# if-amp.net
KiCad netlist of a schematic drawn in Altium Designer
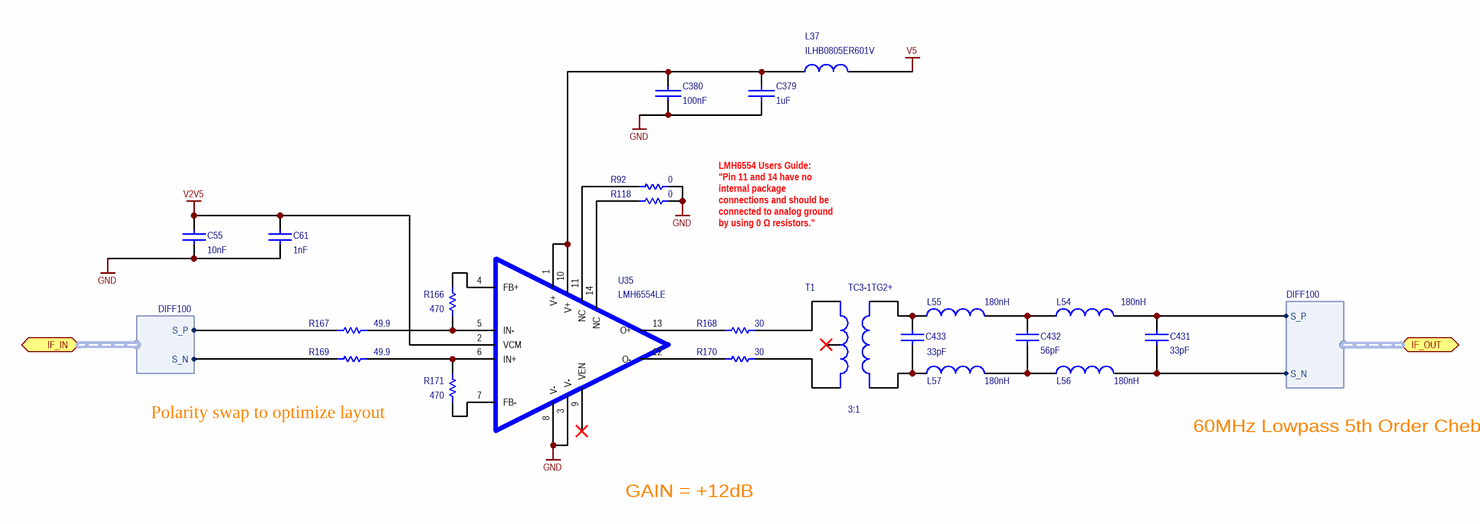
[diagram p0: if-amp.SchDoc]

(export (version "E")
  (design (tool "Eeschema 10.0.6"))
  (components
    (comp (ref "C55")
      (value "10nF")
      (footprint "generic:0402")
      (description "Ceramic Capacitor 10nF ±10% 25V X7R 0402")
      (fields (field (name "VOLTAGE") "25V") (field (name "MANUFACTURER") "Murata"))
      (libsource (lib "Graviton") (part "CAP 0402"))
    )
    (comp (ref "C61")
      (value "1nF")
      (footprint "generic:0402")
      (description "Ceramic Capacitor 1nF ±5% 50V NP0 0402")
      (fields (field (name "VOLTAGE") "50V") (field (name "MANUFACTURER") "Murata"))
      (libsource (lib "Graviton") (part "CAP 0402"))
    )
    (comp (ref "C379")
      (value "1uF")
      (footprint "generic:0402")
      (description "Ceramic Capacitor 1uF ±10% 10V X5R 0402")
      (fields (field (name "MANUFACTURER") "Murata") (field (name "TOLERANCE") "±10%"))
      (libsource (lib "*") (part "CAP"))
    )
    (comp (ref "C380")
      (value "100nF")
      (footprint "generic:0402")
      (description "Ceramic Capacitor 100nF ±10% 16V X7R 0402")
      (fields (field (name "MANUFACTURER") "Murata") (field (name "VOLTAGE") "16V"))
      (libsource (lib "*") (part "CAP"))
    )
    (comp (ref "C431")
      (value "33pF")
      (footprint "generic:0402")
      (description "Ceramic Capacitor 33pF ±5% 50V NP0 0402")
      (fields (field (name "VOLTAGE") "50V") (field (name "MANUFACTURER") "Murata"))
      (libsource (lib "Graviton") (part "CAP 0402"))
    )
    (comp (ref "C432")
      (value "56pF")
      (footprint "generic:0402")
      (description "Ceramic Capacitor 56pF ±5% 50V NP0 0402")
      (fields (field (name "VOLTAGE") "50V") (field (name "MANUFACTURER") "Murata"))
      (libsource (lib "Graviton") (part "CAP 0402"))
    )
    (comp (ref "C433")
      (value "33pF")
      (footprint "generic:0402")
      (description "Ceramic Capacitor 33pF ±5% 50V NP0 0402")
      (fields (field (name "VOLTAGE") "50V") (field (name "MANUFACTURER") "Murata"))
      (libsource (lib "Graviton") (part "CAP 0402"))
    )
    (comp (ref "L37")
      (value "ILHB0805ER601V")
      (footprint "0805")
      (description "Ferrite Bead 600-Ohm @ 100MHz 2A 0805")
      (fields (field (name "MANUFACTURER") "Vishay Dale") (field (name "TOLERANCE") "±25%"))
      (libsource (lib "*") (part "INDUCTANCE1"))
    )
    (comp (ref "L54")
      (value "180nH")
      (footprint "0603")
      (description "Inductor Wirewound 180nH ±2% 0603")
      (fields (field (name "MANUFACTURER") "Murata") (field (name "TOLERANCE") "±2%"))
      (libsource (lib "generic") (part "INDUCTOR"))
    )
    (comp (ref "L55")
      (value "180nH")
      (footprint "0603")
      (description "Inductor Wirewound 180nH ±2% 0603")
      (fields (field (name "MANUFACTURER") "Murata") (field (name "TOLERANCE") "±2%"))
      (libsource (lib "generic") (part "INDUCTOR"))
    )
    (comp (ref "L56")
      (value "180nH")
      (footprint "0603")
      (description "Inductor Wirewound 180nH ±2% 0603")
      (fields (field (name "MANUFACTURER") "Murata") (field (name "TOLERANCE") "±2%"))
      (libsource (lib "generic") (part "INDUCTOR"))
    )
    (comp (ref "L57")
      (value "180nH")
      (footprint "0603")
      (description "Inductor Wirewound 180nH ±2% 0603")
      (fields (field (name "MANUFACTURER") "Murata") (field (name "TOLERANCE") "±2%"))
      (libsource (lib "generic") (part "INDUCTOR"))
    )
    (comp (ref "R92")
      (value "0")
      (footprint "generic:0402")
      (description "Thick Film Resistor Jumper 0402")
      (fields (field (name "MANUFACTURER") "Panasonic") (field (name "Comment") "ERJ-2GE0R00X"))
      (libsource (lib "generic") (part "RES 0402"))
    )
    (comp (ref "R118")
      (value "0")
      (footprint "generic:0402")
      (description "Thick Film Resistor Jumper 0402")
      (fields (field (name "MANUFACTURER") "Panasonic") (field (name "Comment") "ERJ-2GE0R00X"))
      (libsource (lib "generic") (part "RES 0402"))
    )
    (comp (ref "R166")
      (value "470")
      (footprint "generic:0402")
      (description "Thin Film Resistor 470 ±0.1% 0402")
      (fields (field (name "MANUFACTURER") "Panasonic") (field (name "TOLERANCE") "±0.1%"))
      (libsource (lib "Graviton") (part "RES 0402"))
    )
    (comp (ref "R167")
      (value "49.9")
      (footprint "generic:0402")
      (description "Thin Film Resistor 49.9 ±0.1% 0402")
      (fields (field (name "MANUFACTURER") "Panasonic") (field (name "TOLERANCE") "±0.1%"))
      (libsource (lib "Graviton") (part "RES 0402"))
    )
    (comp (ref "R168")
      (value "30")
      (footprint "generic:0402")
      (description "Thin Film Resistor 30 ±0.1% 0402")
      (fields (field (name "MANUFACTURER") "TE Connectivity") (field (name "TOLERANCE") "0.1%"))
      (libsource (lib "Graviton") (part "RES 0402"))
    )
    (comp (ref "R169")
      (value "49.9")
      (footprint "generic:0402")
      (description "Thin Film Resistor 49.9 ±0.1% 0402")
      (fields (field (name "MANUFACTURER") "Panasonic") (field (name "TOLERANCE") "±0.1%"))
      (libsource (lib "Graviton") (part "RES 0402"))
    )
    (comp (ref "R170")
      (value "30")
      (footprint "generic:0402")
      (description "Thin Film Resistor 30 ±0.1% 0402")
      (fields (field (name "MANUFACTURER") "TE Connectivity") (field (name "TOLERANCE") "0.1%"))
      (libsource (lib "Graviton") (part "RES 0402"))
    )
    (comp (ref "R171")
      (value "470")
      (footprint "generic:0402")
      (description "Thin Film Resistor 470 ±0.1% 0402")
      (fields (field (name "MANUFACTURER") "Panasonic") (field (name "TOLERANCE") "±0.1%"))
      (libsource (lib "Graviton") (part "RES 0402"))
    )
    (comp (ref "T1")
      (value "3:1")
      (footprint "AT224-1A")
      (description "RF Transformer 0.4 to 500MHz SMD")
      (fields
        (field (name "MANUFACTURER P/N") "TC3-1TG2+")
        (field (name "MANUFACTURER") "Mini-Circuits")
        (field (name "Comment") "TC3-1TG2+")
      )
      (libsource (lib "phase4") (part "TC1-1TG2+"))
    )
    (comp (ref "U35")
      (value "LMH6554LE")
      (footprint "texas_instruments:NHJ0014A")
      (description "2.8 GHz Ultra Linear Fully Differential Amplifier")
      (fields (field (name "MANUFACTURER") "Texas Instruments"))
      (libsource (lib "ti") (part "LMH6554LE"))
    )
  )
  (nets
    (net (code "3") (name "GND") (class "Default")
      (node (ref "C379") (pin "1") (pinfunction "1_1") (pintype "passive"))
      (node (ref "C380") (pin "1") (pinfunction "1_1") (pintype "passive"))
      (node (ref "C55") (pin "1") (pinfunction "1_1") (pintype "passive"))
      (node (ref "C61") (pin "1") (pinfunction "1_1") (pintype "passive"))
      (node (ref "R118") (pin "2") (pinfunction "2_2") (pintype "passive"))
      (node (ref "R92") (pin "2") (pinfunction "2_2") (pintype "passive"))
      (node (ref "U35") (pin "3") (pinfunction "V-_3") (pintype "passive"))
      (node (ref "U35") (pin "8") (pinfunction "V-_8") (pintype "passive"))
    )
    (net (code "4") (name "Net-(C379-Pad2)") (class "Default")
      (node (ref "C379") (pin "2") (pinfunction "2_2") (pintype "passive"))
      (node (ref "C380") (pin "2") (pinfunction "2_2") (pintype "passive"))
      (node (ref "L37") (pin "1") (pinfunction "1_1") (pintype "passive"))
      (node (ref "U35") (pin "1") (pinfunction "V+_1") (pintype "passive"))
      (node (ref "U35") (pin "10") (pinfunction "V+_10") (pintype "passive"))
    )
    (net (code "5") (name "Net-(C431-Pad1)") (class "Default")
      (node (ref "C431") (pin "1") (pinfunction "1_1") (pintype "passive"))
      (node (ref "L56") (pin "1") (pinfunction "1_1") (pintype "passive"))
    )
    (net (code "6") (name "Net-(C431-Pad2)") (class "Default")
      (node (ref "C431") (pin "2") (pinfunction "2_2") (pintype "passive"))
      (node (ref "L54") (pin "1") (pinfunction "1_1") (pintype "passive"))
    )
    (net (code "7") (name "Net-(C432-Pad1)") (class "Default")
      (node (ref "C432") (pin "1") (pinfunction "1_1") (pintype "passive"))
      (node (ref "L56") (pin "2") (pinfunction "2_2") (pintype "passive"))
      (node (ref "L57") (pin "1") (pinfunction "1_1") (pintype "passive"))
    )
    (net (code "8") (name "Net-(C432-Pad2)") (class "Default")
      (node (ref "C432") (pin "2") (pinfunction "2_2") (pintype "passive"))
      (node (ref "L54") (pin "2") (pinfunction "2_2") (pintype "passive"))
      (node (ref "L55") (pin "1") (pinfunction "1_1") (pintype "passive"))
    )
    (net (code "9") (name "Net-(R92-Pad1)") (class "Default")
      (node (ref "R92") (pin "1") (pinfunction "1_1") (pintype "passive"))
      (node (ref "U35") (pin "11") (pinfunction "NC_11") (pintype "passive"))
    )
    (net (code "10") (name "Net-(R118-Pad1)") (class "Default")
      (node (ref "R118") (pin "1") (pinfunction "1_1") (pintype "passive"))
      (node (ref "U35") (pin "14") (pinfunction "NC_14") (pintype "passive"))
    )
    (net (code "11") (name "Net-(T1-Pri+)") (class "Default")
      (node (ref "C433") (pin "1") (pinfunction "1_1") (pintype "passive"))
      (node (ref "L57") (pin "2") (pinfunction "2_2") (pintype "passive"))
      (node (ref "T1") (pin "6") (pinfunction "Pri+_6") (pintype "passive"))
    )
    (net (code "12") (name "Net-(T1-Pri-)") (class "Default")
      (node (ref "C433") (pin "2") (pinfunction "2_2") (pintype "passive"))
      (node (ref "L55") (pin "2") (pinfunction "2_2") (pintype "passive"))
      (node (ref "T1") (pin "4") (pinfunction "Pri-_4") (pintype "passive"))
    )
    (net (code "13") (name "Net-(T1-Sec+)") (class "Default")
      (node (ref "R170") (pin "1") (pinfunction "1_1") (pintype "passive"))
      (node (ref "T1") (pin "1") (pinfunction "Sec+_1") (pintype "passive"))
    )
    (net (code "14") (name "Net-(T1-Sec-)") (class "Default")
      (node (ref "R168") (pin "1") (pinfunction "1_1") (pintype "passive"))
      (node (ref "T1") (pin "3") (pinfunction "Sec-_3") (pintype "passive"))
    )
    (net (code "15") (name "Net-(U35-FB+)") (class "Default")
      (node (ref "R166") (pin "1") (pinfunction "1_1") (pintype "passive"))
      (node (ref "U35") (pin "4") (pinfunction "FB+_4") (pintype "passive"))
    )
    (net (code "16") (name "Net-(U35-FB-)") (class "Default")
      (node (ref "R171") (pin "2") (pinfunction "2_2") (pintype "passive"))
      (node (ref "U35") (pin "7") (pinfunction "FB-_7") (pintype "passive"))
    )
    (net (code "17") (name "Net-(U35-IN+)") (class "Default")
      (node (ref "R169") (pin "1") (pinfunction "1_1") (pintype "passive"))
      (node (ref "R171") (pin "1") (pinfunction "1_1") (pintype "passive"))
      (node (ref "U35") (pin "6") (pinfunction "IN+_6") (pintype "passive"))
    )
    (net (code "18") (name "Net-(U35-IN-)") (class "Default")
      (node (ref "R166") (pin "2") (pinfunction "2_2") (pintype "passive"))
      (node (ref "R167") (pin "1") (pinfunction "1_1") (pintype "passive"))
      (node (ref "U35") (pin "5") (pinfunction "IN-_5") (pintype "passive"))
    )
    (net (code "19") (name "Net-(U35-O+)") (class "Default")
      (node (ref "R168") (pin "2") (pinfunction "2_2") (pintype "passive"))
      (node (ref "U35") (pin "13") (pinfunction "O+_13") (pintype "passive"))
    )
    (net (code "20") (name "Net-(U35-O-)") (class "Default")
      (node (ref "R170") (pin "2") (pinfunction "2_2") (pintype "passive"))
      (node (ref "U35") (pin "12") (pinfunction "O-_12") (pintype "passive"))
    )
    (net (code "21") (name "V2V5") (class "Default")
      (node (ref "C55") (pin "2") (pinfunction "2_2") (pintype "passive"))
      (node (ref "C61") (pin "2") (pinfunction "2_2") (pintype "passive"))
      (node (ref "U35") (pin "2") (pinfunction "VCM_2") (pintype "passive"))
    )
    (net (code "22") (name "V5") (class "Default")
      (node (ref "L37") (pin "2") (pinfunction "2_2") (pintype "passive"))
    )
    (net (code "23") (name "unconnected-(R167-Pad2)") (class "Default")
      (node (ref "R167") (pin "2") (pinfunction "2_2") (pintype "passive"))
    )
    (net (code "24") (name "unconnected-(R169-Pad2)") (class "Default")
      (node (ref "R169") (pin "2") (pinfunction "2_2") (pintype "passive"))
    )
    (net (code "25") (name "unconnected-(T1-SecCT-Pad2)") (class "Default")
      (node (ref "T1") (pin "2") (pinfunction "SecCT_2") (pintype "passive+no_connect"))
    )
    (net (code "26") (name "unconnected-(U35-VEN-Pad9)") (class "Default")
      (node (ref "U35") (pin "9") (pinfunction "VEN_9") (pintype "passive+no_connect"))
    )
  )
)
